# Adafruit_HUZZAH32_ESP32_Feather.net
KiCad netlist of a schematic drawn in EAGLE
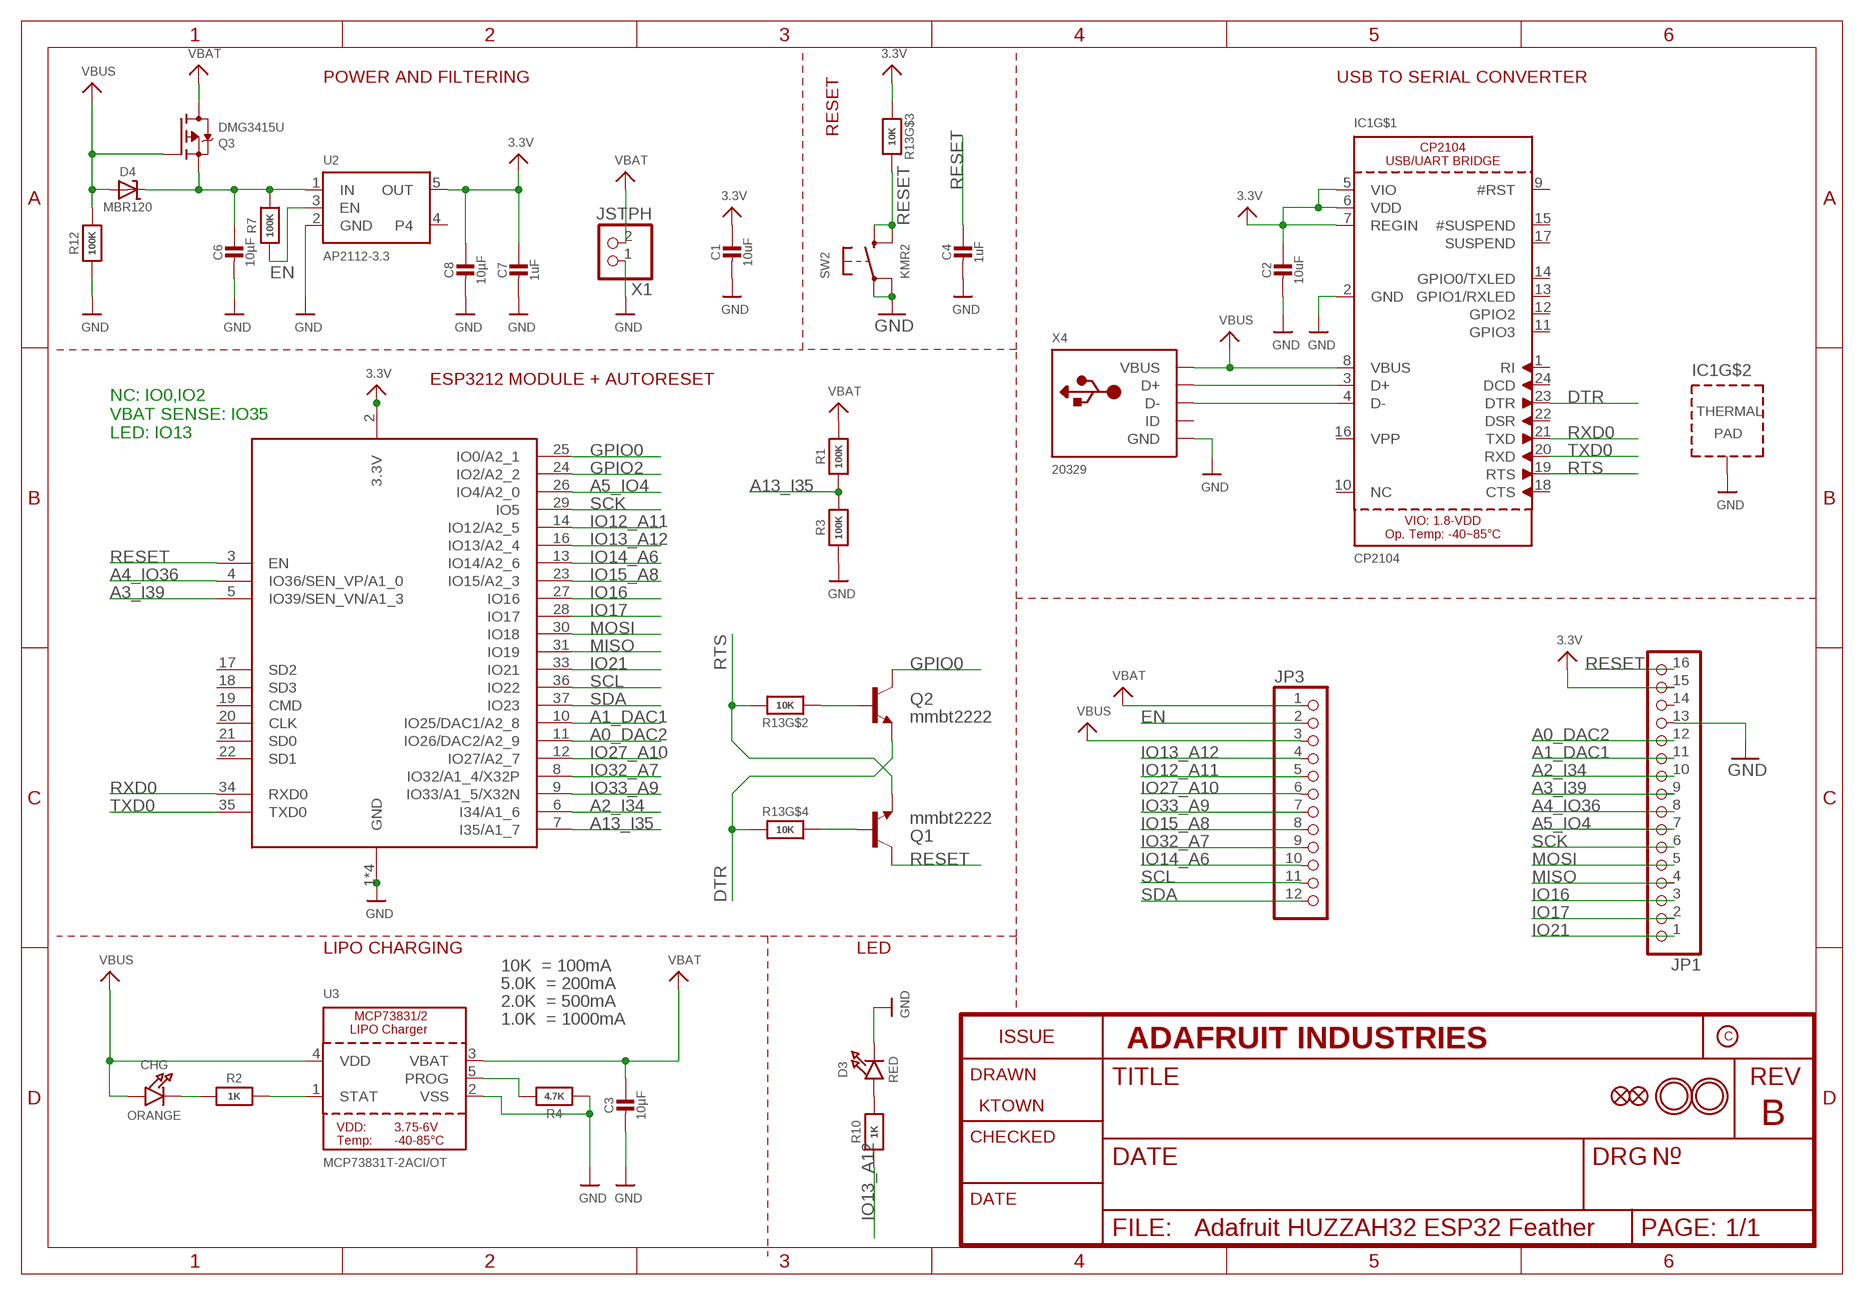
[diagram p0: schematic, sheet 1]

(export (version "E")
  (design (tool "Eeschema 10.0.6"))
  (components
    (comp (ref "C1")
      (value "10uF")
      (footprint "eagle-import:0805-NO")
      (libsource (lib "eagle-import") (part "CAP_CERAMIC0805-NOOUTLINE"))
    )
    (comp (ref "C2")
      (value "10uF")
      (footprint "eagle-import:0805-NO")
      (libsource (lib "eagle-import") (part "CAP_CERAMIC0805-NOOUTLINE"))
    )
    (comp (ref "C3")
      (value "10µF")
      (footprint "eagle-import:0805-NO")
      (libsource (lib "eagle-import") (part "CAP_CERAMIC0805-NOOUTLINE"))
    )
    (comp (ref "C4")
      (value "1uF")
      (footprint "eagle-import:0603-NO")
      (libsource (lib "eagle-import") (part "CAP_CERAMIC0603_NO"))
    )
    (comp (ref "C6")
      (value "10µF")
      (footprint "eagle-import:0805-NO")
      (libsource (lib "eagle-import") (part "CAP_CERAMIC0805-NOOUTLINE"))
    )
    (comp (ref "C7")
      (value "1uF")
      (footprint "eagle-import:0603-NO")
      (libsource (lib "eagle-import") (part "CAP_CERAMIC0603_NO"))
    )
    (comp (ref "C8")
      (value "10µF")
      (footprint "eagle-import:0805-NO")
      (libsource (lib "eagle-import") (part "CAP_CERAMIC0805-NOOUTLINE"))
    )
    (comp (ref "CHG")
      (value "ORANGE")
      (footprint "eagle-import:CHIPLED_0805_NOOUTLINE")
      (libsource (lib "eagle-import") (part "LED0805_NOOUTLINE"))
    )
    (comp (ref "D3")
      (value "RED")
      (footprint "eagle-import:CHIPLED_0805_NOOUTLINE")
      (libsource (lib "eagle-import") (part "LED0805_NOOUTLINE"))
    )
    (comp (ref "D4")
      (value "MBR120")
      (footprint "eagle-import:SOD-123")
      (libsource (lib "eagle-import") (part "DIODE-SCHOTTKYSOD-123"))
    )
    (comp (ref "IC1")
      (value "CP2104")
      (footprint "eagle-import:QFN24_4MM_SMSC")
      (libsource (lib "eagle-import") (part "CP2104"))
    )
    (comp (ref "JP1")
      (value "HEADER-1X16_MIN")
      (footprint "eagle-import:1X16_ROUND_MIN")
      (libsource (lib "eagle-import") (part "HEADER-1X16_MIN"))
    )
    (comp (ref "JP3")
      (value "HEADER-1X12_MIN")
      (footprint "eagle-import:1X12_ROUND_MIN")
      (libsource (lib "eagle-import") (part "HEADER-1X12_MIN"))
    )
    (comp (ref "Q1")
      (value "mmbt2222")
      (footprint "eagle-import:SOT23-3")
      (libsource (lib "eagle-import") (part "TRANSISTOR_NPNSOT23-3"))
    )
    (comp (ref "Q2")
      (value "mmbt2222")
      (footprint "eagle-import:SOT23-3")
      (libsource (lib "eagle-import") (part "TRANSISTOR_NPNSOT23-3"))
    )
    (comp (ref "Q3")
      (value "DMG3415U")
      (footprint "eagle-import:SOT23-R")
      (libsource (lib "eagle-import") (part "MOSFET-P"))
    )
    (comp (ref "R1")
      (value "100K")
      (footprint "eagle-import:0603-NO")
      (libsource (lib "eagle-import") (part "RESISTOR_0603_NOOUT"))
    )
    (comp (ref "R2")
      (value "1K")
      (footprint "eagle-import:0603-NO")
      (libsource (lib "eagle-import") (part "RESISTOR_0603_NOOUT"))
    )
    (comp (ref "R3")
      (value "100K")
      (footprint "eagle-import:0603-NO")
      (libsource (lib "eagle-import") (part "RESISTOR_0603_NOOUT"))
    )
    (comp (ref "R4")
      (value "4.7K")
      (footprint "eagle-import:0603-NO")
      (libsource (lib "eagle-import") (part "RESISTOR_0603_NOOUT"))
    )
    (comp (ref "R7")
      (value "100K")
      (footprint "eagle-import:0603-NO")
      (libsource (lib "eagle-import") (part "RESISTOR_0603_NOOUT"))
    )
    (comp (ref "R10")
      (value "1K")
      (footprint "eagle-import:0603-NO")
      (libsource (lib "eagle-import") (part "RESISTOR_0603_NOOUT"))
    )
    (comp (ref "R12")
      (value "100K")
      (footprint "eagle-import:0603-NO")
      (libsource (lib "eagle-import") (part "RESISTOR_0603_NOOUT"))
    )
    (comp (ref "R13")
      (value "10K")
      (footprint "eagle-import:RESPACK_4X0603")
      (libsource (lib "eagle-import") (part "RESISTOR_4PACK"))
    )
    (comp (ref "SW2")
      (value "KMR2")
      (footprint "eagle-import:BTN_KMR2_4.6X2.8")
      (libsource (lib "eagle-import") (part "SWITCH_TACT_SMT4.6X2.8"))
    )
    (comp (ref "U$31")
      (value "MOUNTINGHOLE2.5")
      (footprint "eagle-import:MOUNTINGHOLE_2.5_PLATED")
      (libsource (lib "eagle-import") (part "MOUNTINGHOLE2.5"))
    )
    (comp (ref "U$32")
      (value "MOUNTINGHOLE2.5")
      (footprint "eagle-import:MOUNTINGHOLE_2.5_PLATED")
      (libsource (lib "eagle-import") (part "MOUNTINGHOLE2.5"))
    )
    (comp (ref "U$34")
      (value "FIDUCIAL_1MM")
      (footprint "eagle-import:FIDUCIAL_1MM")
      (libsource (lib "eagle-import") (part "FIDUCIAL_1MM"))
    )
    (comp (ref "U$35")
      (value "FIDUCIAL_1MM")
      (footprint "eagle-import:FIDUCIAL_1MM")
      (libsource (lib "eagle-import") (part "FIDUCIAL_1MM"))
    )
    (comp (ref "U2")
      (value "AP2112-3.3")
      (footprint "eagle-import:SOT23-5")
      (libsource (lib "eagle-import") (part "VREG_SOT23-5"))
    )
    (comp (ref "U3")
      (value "MCP73831T-2ACI/OT")
      (footprint "eagle-import:SOT23-5")
      (libsource (lib "eagle-import") (part "MCP73831/2"))
    )
    (comp (ref "X1")
      (value "JSTPH")
      (footprint "eagle-import:JSTPH2")
      (libsource (lib "eagle-import") (part "CON_JST_PH_2PIN"))
    )
    (comp (ref "X2")
      (value "ESP32_WROOM32_SKINNY")
      (footprint "eagle-import:WROOM32_SKINNY")
      (libsource (lib "eagle-import") (part "ESP32_WROOM32_SKINNY"))
    )
    (comp (ref "X4")
      (value "20329")
      (footprint "eagle-import:4UCONN_20329_V2")
      (libsource (lib "eagle-import") (part "USB_MICRO_20329_V2"))
    )
  )
  (nets
    (net (code "1") (name "/A0_DAC2") (class "Default")
      (node (ref "JP1") (pin "12") (pinfunction "12_12") (pintype "passive"))
      (node (ref "X2") (pin "11") (pinfunction "IO26/DAC2/A2_9_11") (pintype "bidirectional"))
    )
    (net (code "2") (name "/A1_DAC1") (class "Default")
      (node (ref "JP1") (pin "11") (pinfunction "11_11") (pintype "passive"))
      (node (ref "X2") (pin "10") (pinfunction "IO25/DAC1/A2_8_10") (pintype "bidirectional"))
    )
    (net (code "3") (name "/A2_I34") (class "Default")
      (node (ref "JP1") (pin "10") (pinfunction "10_10") (pintype "passive"))
      (node (ref "X2") (pin "6") (pinfunction "I34/A1_6_6") (pintype "bidirectional"))
    )
    (net (code "4") (name "/A3_I39") (class "Default")
      (node (ref "JP1") (pin "9") (pinfunction "9_9") (pintype "passive"))
      (node (ref "X2") (pin "5") (pinfunction "IO39/SEN_VN/A1_3_5") (pintype "passive"))
    )
    (net (code "5") (name "/A4_IO36") (class "Default")
      (node (ref "JP1") (pin "8") (pinfunction "8_8") (pintype "passive"))
      (node (ref "X2") (pin "4") (pinfunction "IO36/SEN_VP/A1_0_4") (pintype "passive"))
    )
    (net (code "6") (name "/A5_IO4") (class "Default")
      (node (ref "JP1") (pin "7") (pinfunction "7_7") (pintype "passive"))
      (node (ref "X2") (pin "26") (pinfunction "IO4/A2_0_26") (pintype "bidirectional"))
    )
    (net (code "7") (name "/A13_I35") (class "Default")
      (node (ref "R1") (pin "1") (pinfunction "1_1") (pintype "passive"))
      (node (ref "R3") (pin "2") (pinfunction "2_2") (pintype "passive"))
      (node (ref "X2") (pin "7") (pinfunction "I35/A1_7_7") (pintype "bidirectional"))
    )
    (net (code "8") (name "/DTR") (class "Default")
      (node (ref "IC1") (pin "23") (pinfunction "DTR_23") (pintype "output"))
      (node (ref "Q2") (pin "2") (pinfunction "E_2") (pintype "passive"))
      (node (ref "R13") (pin "4") (pinfunction "1_4") (pintype "passive"))
    )
    (net (code "9") (name "/EN") (class "Default")
      (node (ref "JP3") (pin "2") (pinfunction "2_2") (pintype "passive"))
      (node (ref "R7") (pin "1") (pinfunction "1_1") (pintype "passive"))
      (node (ref "U2") (pin "3") (pinfunction "EN_3") (pintype "input"))
    )
    (net (code "10") (name "/GPIO0") (class "Default")
      (node (ref "Q2") (pin "3") (pinfunction "C_3") (pintype "passive"))
      (node (ref "X2") (pin "25") (pinfunction "IO0/A2_1_25") (pintype "bidirectional"))
    )
    (net (code "11") (name "/GPIO2") (class "Default")
      (node (ref "X2") (pin "24") (pinfunction "IO2/A2_2_24") (pintype "bidirectional"))
    )
    (net (code "12") (name "/IO12_A11") (class "Default")
      (node (ref "JP3") (pin "5") (pinfunction "5_5") (pintype "passive"))
      (node (ref "X2") (pin "14") (pinfunction "IO12/A2_5_14") (pintype "bidirectional"))
    )
    (net (code "13") (name "/IO13_A12") (class "Default")
      (node (ref "JP3") (pin "4") (pinfunction "4_4") (pintype "passive"))
      (node (ref "R10") (pin "1") (pinfunction "1_1") (pintype "passive"))
      (node (ref "X2") (pin "16") (pinfunction "IO13/A2_4_16") (pintype "bidirectional"))
    )
    (net (code "14") (name "/IO14_A6") (class "Default")
      (node (ref "JP3") (pin "10") (pinfunction "10_10") (pintype "passive"))
      (node (ref "X2") (pin "13") (pinfunction "IO14/A2_6_13") (pintype "bidirectional"))
    )
    (net (code "15") (name "/IO15_A8") (class "Default")
      (node (ref "JP3") (pin "8") (pinfunction "8_8") (pintype "passive"))
      (node (ref "X2") (pin "23") (pinfunction "IO15/A2_3_23") (pintype "bidirectional"))
    )
    (net (code "16") (name "/IO16") (class "Default")
      (node (ref "JP1") (pin "3") (pinfunction "3_3") (pintype "passive"))
      (node (ref "X2") (pin "27") (pinfunction "IO16_27") (pintype "bidirectional"))
    )
    (net (code "17") (name "/IO17") (class "Default")
      (node (ref "JP1") (pin "2") (pinfunction "2_2") (pintype "passive"))
      (node (ref "X2") (pin "28") (pinfunction "IO17_28") (pintype "bidirectional"))
    )
    (net (code "18") (name "/IO21") (class "Default")
      (node (ref "JP1") (pin "1") (pinfunction "1_1") (pintype "passive"))
      (node (ref "X2") (pin "33") (pinfunction "IO21_33") (pintype "bidirectional"))
    )
    (net (code "19") (name "/IO27_A10") (class "Default")
      (node (ref "JP3") (pin "6") (pinfunction "6_6") (pintype "passive"))
      (node (ref "X2") (pin "12") (pinfunction "IO27/A2_7_12") (pintype "bidirectional"))
    )
    (net (code "20") (name "/IO32_A7") (class "Default")
      (node (ref "JP3") (pin "9") (pinfunction "9_9") (pintype "passive"))
      (node (ref "X2") (pin "8") (pinfunction "IO32/A1_4/X32P_8") (pintype "bidirectional"))
    )
    (net (code "21") (name "/IO33_A9") (class "Default")
      (node (ref "JP3") (pin "7") (pinfunction "7_7") (pintype "passive"))
      (node (ref "X2") (pin "9") (pinfunction "IO33/A1_5/X32N_9") (pintype "bidirectional"))
    )
    (net (code "22") (name "/MISO") (class "Default")
      (node (ref "JP1") (pin "4") (pinfunction "4_4") (pintype "passive"))
      (node (ref "X2") (pin "31") (pinfunction "IO19_31") (pintype "bidirectional"))
    )
    (net (code "23") (name "/MOSI") (class "Default")
      (node (ref "JP1") (pin "5") (pinfunction "5_5") (pintype "passive"))
      (node (ref "X2") (pin "30") (pinfunction "IO18_30") (pintype "bidirectional"))
    )
    (net (code "24") (name "/RESET") (class "Default")
      (node (ref "C4") (pin "1") (pinfunction "1_1") (pintype "passive"))
      (node (ref "JP1") (pin "16") (pinfunction "16_16") (pintype "passive"))
      (node (ref "Q1") (pin "3") (pinfunction "C_3") (pintype "passive"))
      (node (ref "R13") (pin "6") (pinfunction "2_6") (pintype "passive"))
      (node (ref "SW2") (pin "B") (pinfunction "S_B") (pintype "passive"))
      (node (ref "SW2") (pin "B'") (pinfunction "S1_B'") (pintype "passive"))
      (node (ref "X2") (pin "3") (pinfunction "EN_3") (pintype "input"))
    )
    (net (code "25") (name "/RTS") (class "Default")
      (node (ref "IC1") (pin "19") (pinfunction "RTS_19") (pintype "output"))
      (node (ref "Q1") (pin "2") (pinfunction "E_2") (pintype "passive"))
      (node (ref "R13") (pin "7") (pinfunction "2_7") (pintype "passive"))
    )
    (net (code "26") (name "/RXD0") (class "Default")
      (node (ref "IC1") (pin "21") (pinfunction "TXD_21") (pintype "output"))
      (node (ref "X2") (pin "34") (pinfunction "RXD0_34") (pintype "input"))
    )
    (net (code "27") (name "/SCK") (class "Default")
      (node (ref "JP1") (pin "6") (pinfunction "6_6") (pintype "passive"))
      (node (ref "X2") (pin "29") (pinfunction "IO5_29") (pintype "bidirectional"))
    )
    (net (code "28") (name "/SCL") (class "Default")
      (node (ref "JP3") (pin "11") (pinfunction "11_11") (pintype "passive"))
      (node (ref "X2") (pin "36") (pinfunction "IO22_36") (pintype "bidirectional"))
    )
    (net (code "29") (name "/SDA") (class "Default")
      (node (ref "JP3") (pin "12") (pinfunction "12_12") (pintype "passive"))
      (node (ref "X2") (pin "37") (pinfunction "IO23_37") (pintype "bidirectional"))
    )
    (net (code "30") (name "/TXD0") (class "Default")
      (node (ref "IC1") (pin "20") (pinfunction "RXD_20") (pintype "input"))
      (node (ref "X2") (pin "35") (pinfunction "TXD0_35") (pintype "output"))
    )
    (net (code "31") (name "3.3V") (class "Default")
      (node (ref "C1") (pin "1") (pinfunction "1_1") (pintype "passive"))
      (node (ref "C2") (pin "1") (pinfunction "1_1") (pintype "passive"))
      (node (ref "C7") (pin "1") (pinfunction "1_1") (pintype "passive"))
      (node (ref "C8") (pin "1") (pinfunction "1_1") (pintype "passive"))
      (node (ref "IC1") (pin "5") (pinfunction "VIO_5") (pintype "power_in"))
      (node (ref "IC1") (pin "6") (pinfunction "VDD_6") (pintype "power_in"))
      (node (ref "IC1") (pin "7") (pinfunction "REGIN_7") (pintype "power_in"))
      (node (ref "JP1") (pin "15") (pinfunction "15_15") (pintype "passive"))
      (node (ref "R13") (pin "3") (pinfunction "1_3") (pintype "passive"))
      (node (ref "U2") (pin "5") (pinfunction "OUT_5") (pintype "power_in"))
      (node (ref "X2") (pin "2") (pinfunction "3.3V_2") (pintype "passive"))
    )
    (net (code "32") (name "GND") (class "Default")
      (node (ref "C1") (pin "2") (pinfunction "2_2") (pintype "passive"))
      (node (ref "C2") (pin "2") (pinfunction "2_2") (pintype "passive"))
      (node (ref "C3") (pin "2") (pinfunction "2_2") (pintype "passive"))
      (node (ref "C4") (pin "2") (pinfunction "2_2") (pintype "passive"))
      (node (ref "C6") (pin "2") (pinfunction "2_2") (pintype "passive"))
      (node (ref "C7") (pin "2") (pinfunction "2_2") (pintype "passive"))
      (node (ref "C8") (pin "2") (pinfunction "2_2") (pintype "passive"))
      (node (ref "D3") (pin "C") (pinfunction "C_C") (pintype "passive"))
      (node (ref "IC1") (pin "2") (pinfunction "GND_2") (pintype "power_in"))
      (node (ref "IC1") (pin "THERM") (pinfunction "TP_THERM") (pintype "power_in"))
      (node (ref "JP1") (pin "13") (pinfunction "13_13") (pintype "passive"))
      (node (ref "R12") (pin "1") (pinfunction "1_1") (pintype "passive"))
      (node (ref "R3") (pin "1") (pinfunction "1_1") (pintype "passive"))
      (node (ref "R4") (pin "1") (pinfunction "1_1") (pintype "passive"))
      (node (ref "SW2") (pin "A") (pinfunction "P_A") (pintype "passive"))
      (node (ref "SW2") (pin "A'") (pinfunction "P1_A'") (pintype "passive"))
      (node (ref "U2") (pin "2") (pinfunction "GND_2") (pintype "power_in"))
      (node (ref "U3") (pin "2") (pinfunction "VSS_2") (pintype "power_in"))
      (node (ref "X1") (pin "1") (pinfunction "1_1") (pintype "passive"))
      (node (ref "X2") (pin "1") (pinfunction "GND_1") (pintype "passive"))
      (node (ref "X2") (pin "15") (pinfunction "GND_15") (pintype "passive"))
      (node (ref "X2") (pin "38") (pinfunction "GND_38") (pintype "passive"))
      (node (ref "X2") (pin "P$1") (pinfunction "GND_P$1") (pintype "passive"))
      (node (ref "X4") (pin "BASE@1") (pinfunction "GND_BASE@1") (pintype "power_in"))
      (node (ref "X4") (pin "BASE@2") (pinfunction "GND_BASE@2") (pintype "power_in"))
      (node (ref "X4") (pin "GND") (pinfunction "GND_GND") (pintype "power_in"))
      (node (ref "X4") (pin "SPRT@1") (pinfunction "GND_SPRT@1") (pintype "power_in"))
      (node (ref "X4") (pin "SPRT@2") (pinfunction "GND_SPRT@2") (pintype "power_in"))
      (node (ref "X4") (pin "SPRT@3") (pinfunction "GND_SPRT@3") (pintype "power_in"))
      (node (ref "X4") (pin "SPRT@4") (pinfunction "GND_SPRT@4") (pintype "power_in"))
    )
    (net (code "33") (name "Net-(CHG-PadC)") (class "Default")
      (node (ref "CHG") (pin "C") (pinfunction "C_C") (pintype "passive"))
      (node (ref "R2") (pin "1") (pinfunction "1_1") (pintype "passive"))
    )
    (net (code "34") (name "Net-(D3-PadA)") (class "Default")
      (node (ref "D3") (pin "A") (pinfunction "A_A") (pintype "passive"))
      (node (ref "R10") (pin "2") (pinfunction "2_2") (pintype "passive"))
    )
    (net (code "35") (name "Net-(IC1A-D+)") (class "Default")
      (node (ref "IC1") (pin "3") (pinfunction "D+_3") (pintype "bidirectional"))
      (node (ref "X4") (pin "D+") (pinfunction "D+_D+") (pintype "bidirectional"))
    )
    (net (code "36") (name "Net-(IC1A-D-)") (class "Default")
      (node (ref "IC1") (pin "4") (pinfunction "D-_4") (pintype "bidirectional"))
      (node (ref "X4") (pin "D-") (pinfunction "D-_D-") (pintype "bidirectional"))
    )
    (net (code "37") (name "Net-(Q1-B)") (class "Default")
      (node (ref "Q1") (pin "1") (pinfunction "B_1") (pintype "passive"))
      (node (ref "R13") (pin "5") (pinfunction "2_5") (pintype "passive"))
    )
    (net (code "38") (name "Net-(Q2-B)") (class "Default")
      (node (ref "Q2") (pin "1") (pinfunction "B_1") (pintype "passive"))
      (node (ref "R13") (pin "2") (pinfunction "1_2") (pintype "passive"))
    )
    (net (code "39") (name "Net-(Q3-S)") (class "Default")
      (node (ref "C6") (pin "1") (pinfunction "1_1") (pintype "passive"))
      (node (ref "D4") (pin "C") (pinfunction "C_C") (pintype "passive"))
      (node (ref "Q3") (pin "2") (pinfunction "S_2") (pintype "passive"))
      (node (ref "R7") (pin "2") (pinfunction "2_2") (pintype "passive"))
      (node (ref "U2") (pin "1") (pinfunction "IN_1") (pintype "power_in"))
    )
    (net (code "40") (name "Net-(U3-PROG)") (class "Default")
      (node (ref "R4") (pin "2") (pinfunction "2_2") (pintype "passive"))
      (node (ref "U3") (pin "5") (pinfunction "PROG_5") (pintype "input"))
    )
    (net (code "41") (name "Net-(U3-STAT)") (class "Default")
      (node (ref "R2") (pin "2") (pinfunction "2_2") (pintype "passive"))
      (node (ref "U3") (pin "1") (pinfunction "STAT_1") (pintype "output"))
    )
    (net (code "42") (name "VBAT") (class "Default")
      (node (ref "C3") (pin "1") (pinfunction "1_1") (pintype "passive"))
      (node (ref "JP3") (pin "1") (pinfunction "1_1") (pintype "passive"))
      (node (ref "Q3") (pin "3") (pinfunction "D_3") (pintype "passive"))
      (node (ref "R1") (pin "2") (pinfunction "2_2") (pintype "passive"))
      (node (ref "U3") (pin "3") (pinfunction "VBAT_3") (pintype "power_in"))
      (node (ref "X1") (pin "2") (pinfunction "2_2") (pintype "passive"))
    )
    (net (code "43") (name "VBUS") (class "Default")
      (node (ref "CHG") (pin "A") (pinfunction "A_A") (pintype "passive"))
      (node (ref "D4") (pin "A") (pinfunction "A_A") (pintype "passive"))
      (node (ref "IC1") (pin "8") (pinfunction "VBUS_8") (pintype "power_in"))
      (node (ref "JP3") (pin "3") (pinfunction "3_3") (pintype "passive"))
      (node (ref "Q3") (pin "1") (pinfunction "G_1") (pintype "passive"))
      (node (ref "R12") (pin "2") (pinfunction "2_2") (pintype "passive"))
      (node (ref "U3") (pin "4") (pinfunction "VDD_4") (pintype "power_in"))
      (node (ref "X4") (pin "VBUS") (pinfunction "VBUS_VBUS") (pintype "power_in"))
    )
    (net (code "44") (name "unconnected-(IC1A-#RST-Pad9)") (class "Default")
      (node (ref "IC1") (pin "9") (pinfunction "#RST_9") (pintype "bidirectional"))
    )
    (net (code "45") (name "unconnected-(IC1A-#SUSPEND-Pad15)") (class "Default")
      (node (ref "IC1") (pin "15") (pinfunction "#SUSPEND_15") (pintype "output"))
    )
    (net (code "46") (name "unconnected-(IC1A-CTS-Pad18)") (class "Default")
      (node (ref "IC1") (pin "18") (pinfunction "CTS_18") (pintype "input"))
    )
    (net (code "47") (name "unconnected-(IC1A-DCD-Pad24)") (class "Default")
      (node (ref "IC1") (pin "24") (pinfunction "DCD_24") (pintype "input"))
    )
    (net (code "48") (name "unconnected-(IC1A-DSR-Pad22)") (class "Default")
      (node (ref "IC1") (pin "22") (pinfunction "DSR_22") (pintype "input"))
    )
    (net (code "49") (name "unconnected-(IC1A-GPIO0{slash}TXLED-Pad14)") (class "Default")
      (node (ref "IC1") (pin "14") (pinfunction "GPIO0/TXLED_14") (pintype "bidirectional"))
    )
    (net (code "50") (name "unconnected-(IC1A-GPIO1{slash}RXLED-Pad13)") (class "Default")
      (node (ref "IC1") (pin "13") (pinfunction "GPIO1/RXLED_13") (pintype "bidirectional"))
    )
    (net (code "51") (name "unconnected-(IC1A-GPIO2-Pad12)") (class "Default")
      (node (ref "IC1") (pin "12") (pinfunction "GPIO2_12") (pintype "bidirectional"))
    )
    (net (code "52") (name "unconnected-(IC1A-GPIO3-Pad11)") (class "Default")
      (node (ref "IC1") (pin "11") (pinfunction "GPIO3_11") (pintype "bidirectional"))
    )
    (net (code "53") (name "unconnected-(IC1A-NC-Pad10)") (class "Default")
      (node (ref "IC1") (pin "10") (pinfunction "NC_10") (pintype "no_connect"))
    )
    (net (code "54") (name "unconnected-(IC1A-RI-Pad1)") (class "Default")
      (node (ref "IC1") (pin "1") (pinfunction "RI_1") (pintype "input"))
    )
    (net (code "55") (name "unconnected-(IC1A-SUSPEND-Pad17)") (class "Default")
      (node (ref "IC1") (pin "17") (pinfunction "SUSPEND_17") (pintype "output"))
    )
    (net (code "56") (name "unconnected-(IC1A-VPP-Pad16)") (class "Default")
      (node (ref "IC1") (pin "16") (pinfunction "VPP_16") (pintype "bidirectional"))
    )
    (net (code "57") (name "unconnected-(JP1-Pad14)") (class "Default")
      (node (ref "JP1") (pin "14") (pinfunction "14_14") (pintype "passive"))
    )
    (net (code "58") (name "unconnected-(U2-P4-Pad4)") (class "Default")
      (node (ref "U2") (pin "4") (pinfunction "P4_4") (pintype "bidirectional"))
    )
    (net (code "59") (name "unconnected-(X2-CLK-Pad20)") (class "Default")
      (node (ref "X2") (pin "20") (pinfunction "CLK_20") (pintype "bidirectional"))
    )
    (net (code "60") (name "unconnected-(X2-CMD-Pad19)") (class "Default")
      (node (ref "X2") (pin "19") (pinfunction "CMD_19") (pintype "bidirectional"))
    )
    (net (code "61") (name "unconnected-(X2-SD0-Pad21)") (class "Default")
      (node (ref "X2") (pin "21") (pinfunction "SD0_21") (pintype "bidirectional"))
    )
    (net (code "62") (name "unconnected-(X2-SD1-Pad22)") (class "Default")
      (node (ref "X2") (pin "22") (pinfunction "SD1_22") (pintype "bidirectional"))
    )
    (net (code "63") (name "unconnected-(X2-SD2-Pad17)") (class "Default")
      (node (ref "X2") (pin "17") (pinfunction "SD2_17") (pintype "bidirectional"))
    )
    (net (code "64") (name "unconnected-(X2-SD3-Pad18)") (class "Default")
      (node (ref "X2") (pin "18") (pinfunction "SD3_18") (pintype "bidirectional"))
    )
    (net (code "65") (name "unconnected-(X4-PadID)") (class "Default")
      (node (ref "X4") (pin "ID") (pinfunction "ID_ID") (pintype "bidirectional"))
    )
  )
)
